# Power_Supply.net
KiCad netlist of a schematic drawn in Altium Designer
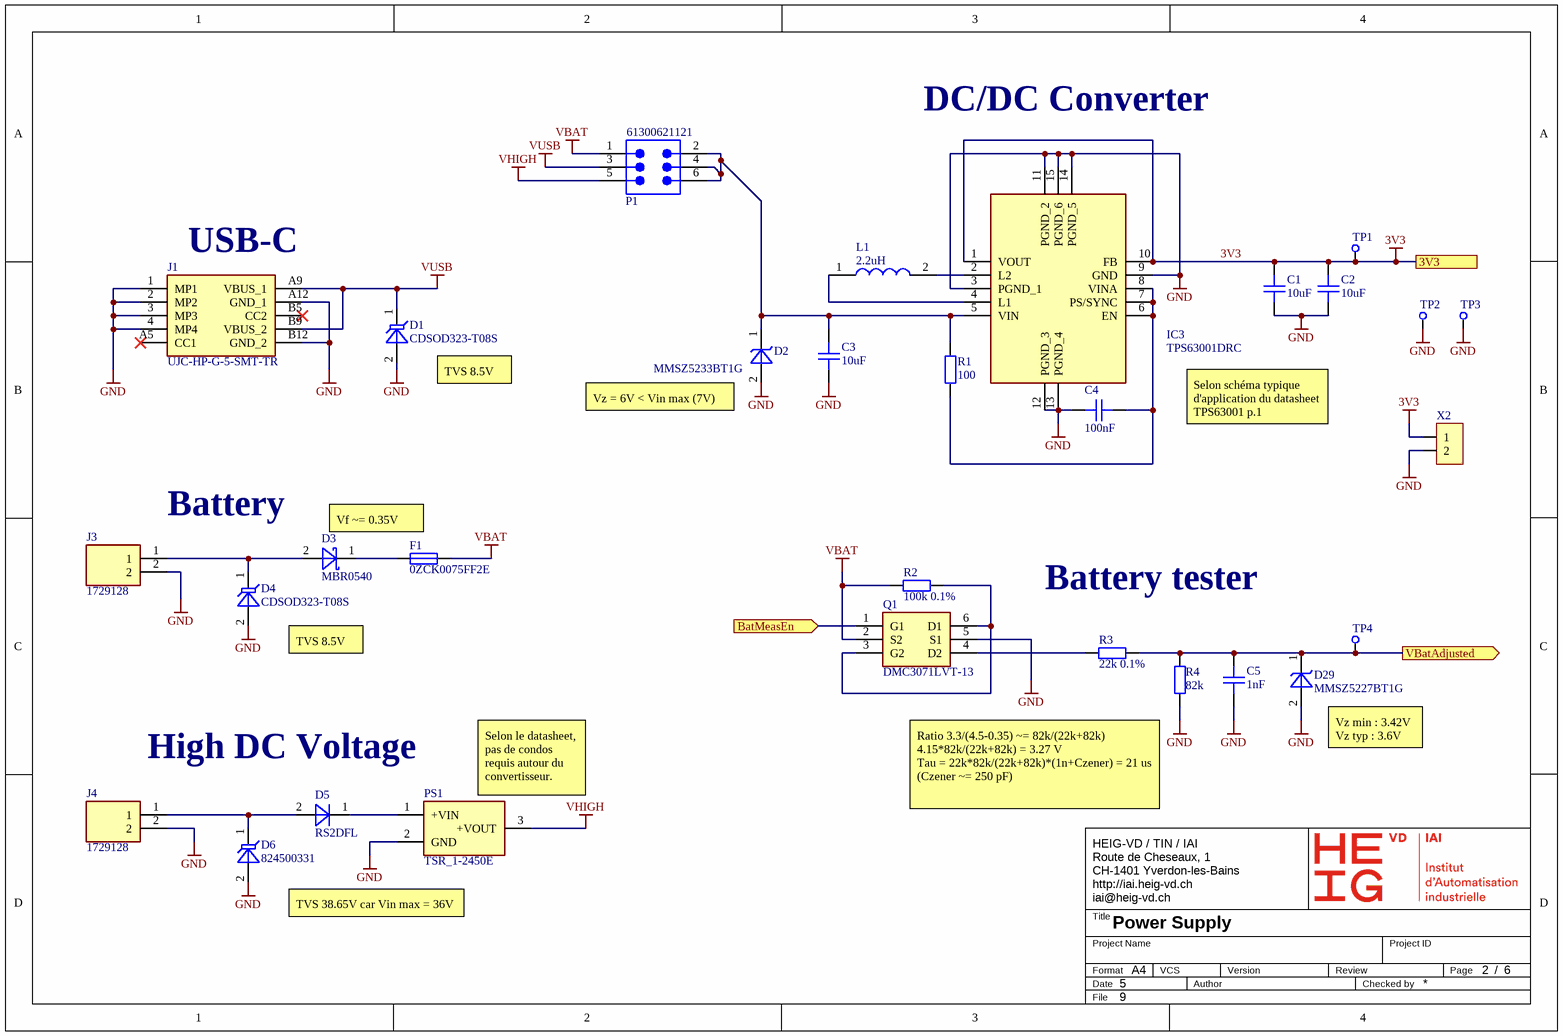
[diagram p0: Power_Supply.SchDoc]

(export (version "E")
  (design (tool "Eeschema 10.0.6"))
  (components
    (comp (ref "C1")
      (value "10uF")
      (footprint "CAPC3216X18N")
      (description "10 µF ±10% 50V Ceramic Capacitor X7R 1206 (3216 Metric)")
      (fields (field (name "TOLERANCE") "10%"))
      (libsource (lib "HEIG-VD Pro") (part "Capacitor"))
    )
    (comp (ref "C2")
      (value "10uF")
      (footprint "CAPC3216X18N")
      (description "10 µF ±10% 50V Ceramic Capacitor X7R 1206 (3216 Metric)")
      (fields (field (name "TOLERANCE") "10%"))
      (libsource (lib "HEIG-VD Pro") (part "Capacitor"))
    )
    (comp (ref "C3")
      (value "10uF")
      (footprint "CAPC3216X18N")
      (description "10 µF ±10% 50V Ceramic Capacitor X7R 1206 (3216 Metric)")
      (fields (field (name "TOLERANCE") "10%") (field (name "MOUSER PART NUMBER") "187-CL31B106KBHNNNE"))
      (libsource (lib "HEIG-VD Pro") (part "Capacitor"))
    )
    (comp (ref "C4")
      (value "100nF")
      (footprint "CAPC1005X05N")
      (description "100nF 10% 50V Ceramic Capacitor X8L 0402 (1005 Metric)")
      (fields (field (name "TOLERANCE") "10%"))
      (libsource (lib "HEIG-VD Pro") (part "Capacitor"))
    )
    (comp (ref "C5")
      (value "1nF")
      (footprint "CAPC1005X05N")
      (description "1nF 20% 50V Ceramic Capacitor X7R 0402 (1005 Metric)")
      (fields (field (name "TOLERANCE") "20%"))
      (libsource (lib "HEIG-VD Pro") (part "Capacitor"))
    )
    (comp (ref "D1")
      (value "CDSOD323-T08S")
      (footprint "SODFL250X110-2N")
      (fields
        (field (name "MOUSER PART NUMBER") "652-CDSOD323-T08SC")
        (field (name "MANUFACTURER_PART_NUMBER") "CDSOD323-T08SC")
      )
      (libsource (lib "HEIG-VD iAi") (part "Diode TVS"))
    )
    (comp (ref "D2")
      (value "MMSZ5233BT1G")
      (footprint "SOD3717X135")
      (description "Zener Diode 6V 500 mW ±5% Surface Mount SOD-123")
      (fields (field (name "POWER") "500mW") (field (name "TOLERANCE") "5%"))
      (libsource (lib "HEIG-VD Pro") (part "Diode Zener"))
    )
    (comp (ref "D3")
      (value "MBR0540")
      (footprint "SODFL371X135-2N")
      (description "DIODE SCHOTTKY 40V 500MA SOD123")
      (libsource (lib "HEIG-VD Pro") (part "Diode Schottky"))
    )
    (comp (ref "D4")
      (value "CDSOD323-T08S")
      (footprint "SODFL250X110-2N")
      (libsource (lib "HEIG-VD iAi") (part "Diode TVS"))
    )
    (comp (ref "D5")
      (value "RS2DFL")
      (footprint "SODFL375X120-2N")
      (description "Rectifier Diode, 1 Phase, 1 Element, 2A, 200V V(RRM), Silicon")
      (libsource (lib "HEIG-VD iAi") (part "Diode"))
    )
    (comp (ref "D6")
      (value "824500331")
      (footprint "DIOM4227X25N")
      (description "Trans Voltage Suppressor Diode, 400W, 33V V(RWM), Unidirectional")
      (libsource (lib "HEIG-VD iAi") (part "Diode TVS"))
    )
    (comp (ref "D29")
      (value "MMSZ5227BT1G")
      (footprint "SOD3717X135")
      (description "Zener Diode 3.6V 500 mW ±5% Surface Mount SOD-123")
      (fields (field (name "POWER") "500mW") (field (name "TOLERANCE") "5%"))
      (libsource (lib "HEIG-VD iAi") (part "Diode Zener"))
    )
    (comp (ref "F1")
      (value "0ZCK0075FF2E")
      (footprint "RESC2012X05N")
      (description "Polymeric PTC Resettable Fuse 6V 750 mA Ih Surface Mount 0805 (2012 Metric), Concave")
      (libsource (lib "HEIG-VD Pro") (part "Fuse"))
    )
    (comp (ref "IC3")
      (value "TPS63001DRC")
      (footprint "TPS63002DRCT")
      (description "Integrated Circuit")
      (libsource (lib "Rainette") (part "TPS63001DRC"))
    )
    (comp (ref "J1")
      (value "UJC-HP-G-5-SMT-TR")
      (footprint "UJCHPG5SMTTR")
      (description "Connector")
      (fields (field (name "MOUSER PART NUMBER") "179-UJCHPG5SMTTR"))
      (libsource (lib "Rainette") (part "UJC-HP-G-5-SMT-TR"))
    )
    (comp (ref "J3")
      (value "1729128")
      (footprint "1729128")
      (description "Connector")
      (fields (field (name "MOUSER PART NUMBER") "651-1729128"))
      (libsource (lib "Rainette") (part "1729128"))
    )
    (comp (ref "J4")
      (value "1729128")
      (footprint "1729128")
      (description "Connector")
      (fields (field (name "MOUSER PART NUMBER") "651-1729128"))
      (libsource (lib "Rainette") (part "1729128"))
    )
    (comp (ref "L1")
      (value "2.2uH")
      (footprint "LPS3015")
      (description "Inductor\r\nLPS3015-222MLB")
      (fields
        (field (name "MANUFACTURER_PART_NUMBER") "LPS3015-222MLB")
        (field (name "MOUSER PART NUMBER") "994-LPS3015-222MLB")
      )
      (libsource (lib "Rainette") (part "LPS3015-222MLB"))
    )
    (comp (ref "P1")
      (value "61300621121")
      (footprint "61300621121")
      (description "WR-PHD Pin Header, THT, Vertical, pitch 2.54mm, 2 Row, 6P")
      (fields (field (name "MANUFACTURER") "Wurth Elektronik"))
      (libsource (lib "Altium_WR-PHD (rev24a)") (part "61300621121"))
    )
    (comp (ref "PS1")
      (value "TSR_1-2450E")
      (footprint "TSR12450E")
      (description "DC/DC Converter \r\n7-36 V -> 5V")
      (fields
        (field (name "MANUFACTURER_PART_NUMBER") "TSR 1-2450E")
        (field (name "MOUSER PART NUMBER") "495-TSR1-2450E")
      )
      (libsource (lib "Rainette") (part "TSR_1-2450E"))
    )
    (comp (ref "Q1")
      (value "DMC3071LVT-13")
      (footprint "SOT95P280X100-6N")
      (description "MOSFET Pair (N/P-Channel)")
      (fields (field (name "MOUSER PART NUMBER") "621-DMC3071LVT-13"))
      (libsource (lib "Rainette") (part "DMC3071LVT-13"))
    )
    (comp (ref "R1")
      (value "100")
      (footprint "RESC1005X04N")
      (description "100 Ohms 0402\r\nCRCW0402100RFKEDC")
      (fields (field (name "POWER") "62.5mW") (field (name "TOLERANCE") "1%"))
      (libsource (lib "HEIG-VD iAi") (part "Resistor"))
    )
    (comp (ref "R2")
      (value "100k 0.1%")
      (footprint "RESC1608X04N")
      (description "100 kOhms ±0.1% 0.1W, 1/10W Chip Resistor 0603 (1608 Metric) Thin Film")
      (fields (field (name "POWER") "100mW") (field (name "TOLERANCE") "0.1%"))
      (libsource (lib "HEIG-VD Pro") (part "Resistor"))
    )
    (comp (ref "R3")
      (value "22k 0.1%")
      (footprint "RESC1005X04N")
      (description "22 kOhms ±0.1% 0.063W, 1/16W Chip Resistor 0402 (1005 Metric) Thin Film\r\nRT0402BRD0722KL")
      (fields (field (name "TOLERANCE") "0.1%") (field (name "POWER") "63mW"))
      (libsource (lib "") (part "Resistor_1"))
    )
    (comp (ref "R4")
      (value "82k")
      (footprint "RESC3216X06N")
      (fields (field (name "TOLERANCE") "1%") (field (name "POWER") "250mW"))
      (libsource (lib "HEIG-VD iAi") (part "Resistor"))
    )
    (comp (ref "TP1")
      (value "ICT Test Point - TH Round Pad")
      (footprint "TPICTTH09N")
      (description "Through hole test point round pad for in-circuit test")
      (libsource (lib "HEIG-VD Pro") (part "Test Point ICT THT"))
    )
    (comp (ref "TP2")
      (value "ICT Test Point - TH Round Pad")
      (footprint "TPICTTH09N")
      (description "Through hole test point round pad for in-circuit test")
      (libsource (lib "HEIG-VD Pro") (part "Test Point ICT THT"))
    )
    (comp (ref "TP3")
      (value "ICT Test Point - TH Round Pad")
      (footprint "TPICTTH09N")
      (description "Through hole test point round pad for in-circuit test")
      (libsource (lib "HEIG-VD Pro") (part "Test Point ICT THT"))
    )
    (comp (ref "TP4")
      (value "ICT Test Point - TH Round Pad")
      (footprint "TPICTTH09N")
      (description "Through hole test point round pad for in-circuit test")
      (libsource (lib "HEIG-VD Pro") (part "Test Point ICT THT"))
    )
    (comp (ref "X2")
      (value "CONN HEADER VERT 2POS 2.54MM")
      (footprint "CONN HEADER VERT 2POS 2.54MM")
      (description "Connector Header Through Hole 2 position 0.100\" (2.54mm)")
      (libsource (lib "HEIG-VD Pro") (part "CONN HEADER VERT 2POS 2.54MM"))
    )
  )
  (nets
    (net (code "1") (name "/BatMeasEn") (class "Default")
      (node (ref "Q1") (pin "1") (pinfunction "G1_1") (pintype "passive"))
    )
    (net (code "2") (name "/VBatAdjusted") (class "Default")
      (node (ref "C5") (pin "2") (pinfunction "2_2") (pintype "passive"))
      (node (ref "D29") (pin "1") (pinfunction "K_1") (pintype "passive"))
      (node (ref "R3") (pin "2") (pinfunction "2_2") (pintype "passive"))
      (node (ref "R4") (pin "2") (pinfunction "2_2") (pintype "passive"))
      (node (ref "TP4") (pin "1") (pinfunction "1_1") (pintype "passive"))
    )
    (net (code "3") (name "3V3") (class "Default")
      (node (ref "C1") (pin "2") (pinfunction "2_2") (pintype "passive"))
      (node (ref "C2") (pin "2") (pinfunction "2_2") (pintype "passive"))
      (node (ref "IC3") (pin "1") (pinfunction "VOUT_1") (pintype "passive"))
      (node (ref "IC3") (pin "10") (pinfunction "FB_10") (pintype "passive"))
      (node (ref "TP1") (pin "1") (pinfunction "1_1") (pintype "passive"))
      (node (ref "X2") (pin "1") (pinfunction "1_1") (pintype "passive"))
    )
    (net (code "4") (name "GND") (class "Default")
      (node (ref "C1") (pin "1") (pinfunction "1_1") (pintype "passive"))
      (node (ref "C2") (pin "1") (pinfunction "1_1") (pintype "passive"))
      (node (ref "C3") (pin "1") (pinfunction "1_1") (pintype "passive"))
      (node (ref "C4") (pin "1") (pinfunction "1_1") (pintype "passive"))
      (node (ref "C5") (pin "1") (pinfunction "1_1") (pintype "passive"))
      (node (ref "D1") (pin "2") (pinfunction "A_2") (pintype "passive"))
      (node (ref "D2") (pin "2") (pinfunction "A_2") (pintype "passive"))
      (node (ref "D29") (pin "2") (pinfunction "A_2") (pintype "passive"))
      (node (ref "D4") (pin "2") (pinfunction "A_2") (pintype "passive"))
      (node (ref "D6") (pin "2") (pinfunction "A_2") (pintype "passive"))
      (node (ref "IC3") (pin "11") (pinfunction "PGND_2_11") (pintype "passive"))
      (node (ref "IC3") (pin "12") (pinfunction "PGND_3_12") (pintype "passive"))
      (node (ref "IC3") (pin "13") (pinfunction "PGND_4_13") (pintype "passive"))
      (node (ref "IC3") (pin "14") (pinfunction "PGND_5_14") (pintype "passive"))
      (node (ref "IC3") (pin "15") (pinfunction "PGND_6_15") (pintype "passive"))
      (node (ref "IC3") (pin "3") (pinfunction "PGND_1_3") (pintype "passive"))
      (node (ref "IC3") (pin "9") (pinfunction "GND_9") (pintype "passive"))
      (node (ref "J1") (pin "1") (pinfunction "MP1_1") (pintype "passive"))
      (node (ref "J1") (pin "2") (pinfunction "MP2_2") (pintype "passive"))
      (node (ref "J1") (pin "3") (pinfunction "MP3_3") (pintype "passive"))
      (node (ref "J1") (pin "4") (pinfunction "MP4_4") (pintype "passive"))
      (node (ref "J1") (pin "A12") (pinfunction "GND_1_A12") (pintype "passive"))
      (node (ref "J1") (pin "B12") (pinfunction "GND_2_B12") (pintype "passive"))
      (node (ref "J3") (pin "2") (pinfunction "2_2") (pintype "passive"))
      (node (ref "J4") (pin "2") (pinfunction "2_2") (pintype "passive"))
      (node (ref "PS1") (pin "2") (pinfunction "GND_2") (pintype "passive"))
      (node (ref "Q1") (pin "5") (pinfunction "S1_5") (pintype "passive"))
      (node (ref "R4") (pin "1") (pinfunction "1_1") (pintype "passive"))
      (node (ref "TP2") (pin "1") (pinfunction "1_1") (pintype "passive"))
      (node (ref "TP3") (pin "1") (pinfunction "1_1") (pintype "passive"))
      (node (ref "X2") (pin "2") (pinfunction "2_2") (pintype "passive"))
    )
    (net (code "5") (name "Net-(D2-K)") (class "Default")
      (node (ref "C3") (pin "2") (pinfunction "2_2") (pintype "passive"))
      (node (ref "D2") (pin "1") (pinfunction "K_1") (pintype "passive"))
      (node (ref "IC3") (pin "5") (pinfunction "VIN_5") (pintype "passive"))
      (node (ref "P1") (pin "2") (pinfunction "2_2") (pintype "passive"))
      (node (ref "P1") (pin "4") (pinfunction "4_4") (pintype "passive"))
      (node (ref "P1") (pin "6") (pinfunction "6_6") (pintype "passive"))
      (node (ref "R1") (pin "2") (pinfunction "2_2") (pintype "passive"))
    )
    (net (code "6") (name "Net-(D3-A)") (class "Default")
      (node (ref "D3") (pin "2") (pinfunction "A_2") (pintype "passive"))
      (node (ref "D4") (pin "1") (pinfunction "K_1") (pintype "passive"))
      (node (ref "J3") (pin "1") (pinfunction "1_1") (pintype "passive"))
    )
    (net (code "7") (name "Net-(D3-K)") (class "Default")
      (node (ref "D3") (pin "1") (pinfunction "K_1") (pintype "passive"))
      (node (ref "F1") (pin "1") (pinfunction "1_1") (pintype "passive"))
    )
    (net (code "8") (name "Net-(D5-A)") (class "Default")
      (node (ref "D5") (pin "2") (pinfunction "A_2") (pintype "passive"))
      (node (ref "D6") (pin "1") (pinfunction "K_1") (pintype "passive"))
      (node (ref "J4") (pin "1") (pinfunction "1_1") (pintype "passive"))
    )
    (net (code "9") (name "Net-(D5-K)") (class "Default")
      (node (ref "D5") (pin "1") (pinfunction "K_1") (pintype "passive"))
      (node (ref "PS1") (pin "1") (pinfunction "+VIN_1") (pintype "passive"))
    )
    (net (code "10") (name "Net-(IC3-EN)") (class "Default")
      (node (ref "C4") (pin "2") (pinfunction "2_2") (pintype "passive"))
      (node (ref "IC3") (pin "6") (pinfunction "EN_6") (pintype "passive"))
      (node (ref "IC3") (pin "7") (pinfunction "PS/SYNC_7") (pintype "passive"))
      (node (ref "IC3") (pin "8") (pinfunction "VINA_8") (pintype "passive"))
      (node (ref "R1") (pin "1") (pinfunction "1_1") (pintype "passive"))
    )
    (net (code "11") (name "Net-(IC3-L1)") (class "Default")
      (node (ref "IC3") (pin "4") (pinfunction "L1_4") (pintype "passive"))
      (node (ref "L1") (pin "1") (pinfunction "1_1") (pintype "passive"))
    )
    (net (code "12") (name "Net-(IC3-L2)") (class "Default")
      (node (ref "IC3") (pin "2") (pinfunction "L2_2") (pintype "passive"))
      (node (ref "L1") (pin "2") (pinfunction "2_2") (pintype "passive"))
    )
    (net (code "13") (name "Net-(Q1-D1)") (class "Default")
      (node (ref "Q1") (pin "3") (pinfunction "G2_3") (pintype "passive"))
      (node (ref "Q1") (pin "6") (pinfunction "D1_6") (pintype "passive"))
      (node (ref "R2") (pin "1") (pinfunction "1_1") (pintype "passive"))
    )
    (net (code "14") (name "Net-(Q1-D2)") (class "Default")
      (node (ref "Q1") (pin "4") (pinfunction "D2_4") (pintype "passive"))
      (node (ref "R3") (pin "1") (pinfunction "1_1") (pintype "passive"))
    )
    (net (code "15") (name "VBAT") (class "Default")
      (node (ref "F1") (pin "2") (pinfunction "2_2") (pintype "passive"))
      (node (ref "P1") (pin "1") (pinfunction "1_1") (pintype "passive"))
      (node (ref "Q1") (pin "2") (pinfunction "S2_2") (pintype "passive"))
      (node (ref "R2") (pin "2") (pinfunction "2_2") (pintype "passive"))
    )
    (net (code "16") (name "VHIGH") (class "Default")
      (node (ref "P1") (pin "5") (pinfunction "5_5") (pintype "passive"))
      (node (ref "PS1") (pin "3") (pinfunction "+VOUT_3") (pintype "passive"))
    )
    (net (code "17") (name "VUSB") (class "Default")
      (node (ref "D1") (pin "1") (pinfunction "K_1") (pintype "passive"))
      (node (ref "J1") (pin "A9") (pinfunction "VBUS_1_A9") (pintype "passive"))
      (node (ref "J1") (pin "B9") (pinfunction "VBUS_2_B9") (pintype "passive"))
      (node (ref "P1") (pin "3") (pinfunction "3_3") (pintype "passive"))
    )
    (net (code "18") (name "unconnected-(J1-CC1-PadA5)") (class "Default")
      (node (ref "J1") (pin "A5") (pinfunction "CC1_A5") (pintype "passive+no_connect"))
    )
    (net (code "19") (name "unconnected-(J1-CC2-PadB5)") (class "Default")
      (node (ref "J1") (pin "B5") (pinfunction "CC2_B5") (pintype "passive+no_connect"))
    )
  )
)
